# mic-preamp.net
KiCad netlist of a schematic drawn in EAGLE
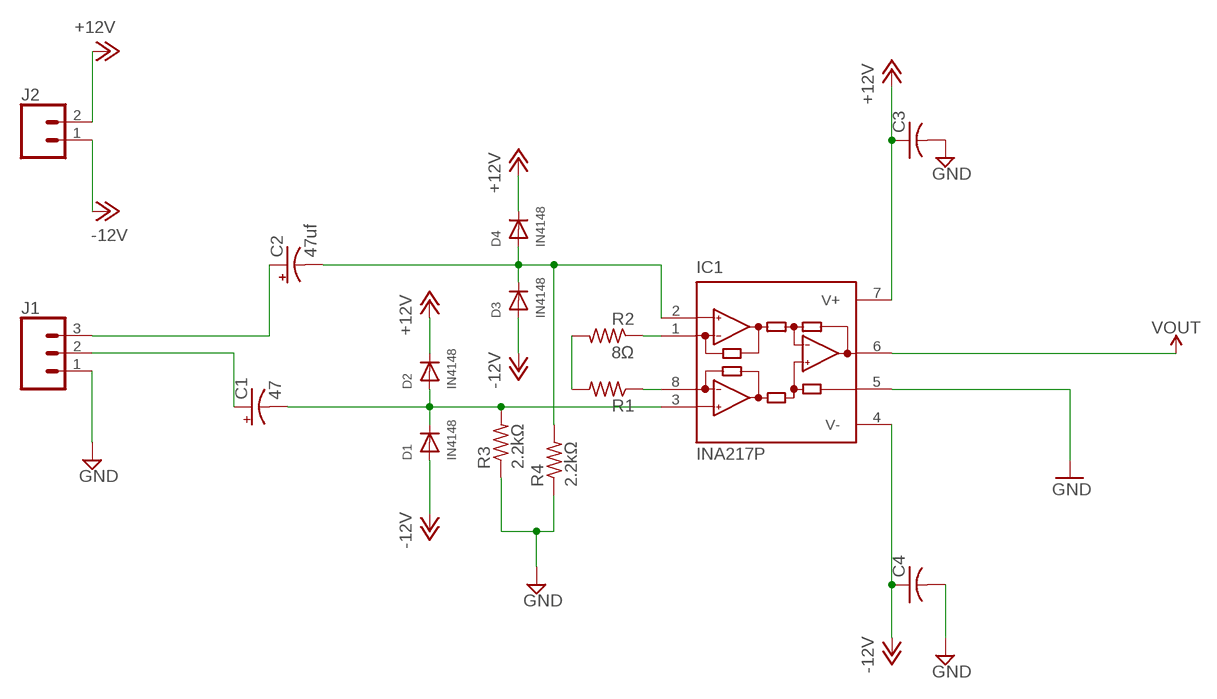
[diagram p0: schematic, sheet 1]

(export (version "E")
  (design (tool "Eeschema 10.0.6"))
  (components
    (comp (ref "C1")
      (value "47")
      (footprint "eagle-import:E7,5-16")
      (libsource (lib "eagle-import") (part "CPOL-USE7.5-16"))
    )
    (comp (ref "C2")
      (value "47uf")
      (footprint "eagle-import:E7,5-16")
      (libsource (lib "eagle-import") (part "CPOL-USE7.5-16"))
    )
    (comp (ref "C3")
      (value "C-US025-024X044")
      (footprint "eagle-import:C025-024X044")
      (libsource (lib "eagle-import") (part "C-US025-024X044"))
    )
    (comp (ref "C4")
      (value "C-US025-024X044")
      (footprint "eagle-import:C025-024X044")
      (libsource (lib "eagle-import") (part "C-US025-024X044"))
    )
    (comp (ref "D1")
      (value "IN4148")
      (footprint "eagle-import:DO-1N4148")
      (libsource (lib "eagle-import") (part "DIODEDO-1N4148"))
    )
    (comp (ref "D2")
      (value "IN4148")
      (footprint "eagle-import:DO-1N4148")
      (libsource (lib "eagle-import") (part "DIODEDO-1N4148"))
    )
    (comp (ref "D3")
      (value "IN4148")
      (footprint "eagle-import:DO-1N4148")
      (libsource (lib "eagle-import") (part "DIODEDO-1N4148"))
    )
    (comp (ref "D4")
      (value "IN4148")
      (footprint "eagle-import:DO-1N4148")
      (libsource (lib "eagle-import") (part "DIODEDO-1N4148"))
    )
    (comp (ref "IC1")
      (value "INA217P")
      (footprint "eagle-import:DIL08")
      (fields (field (name "MF") "TEXAS INSTRUMENTS") (field (name "MPN") "INA217AIP"))
      (libsource (lib "eagle-import") (part "INA217P"))
    )
    (comp (ref "J1")
      (value "CONN_03JST-PTH")
      (footprint "eagle-import:JST-3-PTH")
      (libsource (lib "eagle-import") (part "CONN_03JST-PTH"))
    )
    (comp (ref "J2")
      (value "CONN_02POLAR")
      (footprint "eagle-import:MOLEX-1X2")
      (libsource (lib "eagle-import") (part "CONN_02POLAR"))
    )
    (comp (ref "R1")
      (value "R-US_0204/7")
      (footprint "eagle-import:0204_7")
      (libsource (lib "eagle-import") (part "R-US_0204/7"))
    )
    (comp (ref "R2")
      (value "8Ω")
      (footprint "eagle-import:0204_7")
      (libsource (lib "eagle-import") (part "R-US_0204/7"))
    )
    (comp (ref "R3")
      (value "2.2kΩ")
      (footprint "eagle-import:0204_7")
      (libsource (lib "eagle-import") (part "R-US_0204/7"))
    )
    (comp (ref "R4")
      (value "2.2kΩ")
      (footprint "eagle-import:0204_7")
      (libsource (lib "eagle-import") (part "R-US_0204/7"))
    )
  )
  (nets
    (net (code "1") (name "+12V") (class "Default")
      (node (ref "C3") (pin "1") (pinfunction "1_1") (pintype "passive"))
      (node (ref "D2") (pin "C") (pinfunction "C_C") (pintype "passive"))
      (node (ref "D4") (pin "C") (pinfunction "C_C") (pintype "passive"))
      (node (ref "IC1") (pin "7") (pinfunction "V+_7") (pintype "power_in"))
      (node (ref "J2") (pin "2") (pinfunction "2_2") (pintype "passive"))
    )
    (net (code "2") (name "-12V") (class "Default")
      (node (ref "C4") (pin "1") (pinfunction "1_1") (pintype "passive"))
      (node (ref "D1") (pin "A") (pinfunction "A_A") (pintype "passive"))
      (node (ref "D3") (pin "A") (pinfunction "A_A") (pintype "passive"))
      (node (ref "IC1") (pin "4") (pinfunction "V-_4") (pintype "power_in"))
      (node (ref "J2") (pin "1") (pinfunction "1_1") (pintype "passive"))
    )
    (net (code "3") (name "GND") (class "Default")
      (node (ref "C3") (pin "2") (pinfunction "2_2") (pintype "passive"))
      (node (ref "C4") (pin "2") (pinfunction "2_2") (pintype "passive"))
      (node (ref "IC1") (pin "5") (pinfunction "REF_5") (pintype "passive"))
      (node (ref "J1") (pin "1") (pinfunction "1_1") (pintype "passive"))
      (node (ref "R3") (pin "1") (pinfunction "1_1") (pintype "passive"))
      (node (ref "R4") (pin "1") (pinfunction "1_1") (pintype "passive"))
    )
    (net (code "4") (name "Net-(C1-Pad+)") (class "Default")
      (node (ref "C1") (pin "+") (pinfunction "+_+") (pintype "passive"))
      (node (ref "J1") (pin "2") (pinfunction "2_2") (pintype "passive"))
    )
    (net (code "5") (name "Net-(C2-Pad+)") (class "Default")
      (node (ref "C2") (pin "+") (pinfunction "+_+") (pintype "passive"))
      (node (ref "J1") (pin "3") (pinfunction "3_3") (pintype "passive"))
    )
    (net (code "6") (name "Net-(IC1-+IN)") (class "Default")
      (node (ref "C1") (pin "-") (pinfunction "-_-") (pintype "passive"))
      (node (ref "D1") (pin "C") (pinfunction "C_C") (pintype "passive"))
      (node (ref "D2") (pin "A") (pinfunction "A_A") (pintype "passive"))
      (node (ref "IC1") (pin "3") (pinfunction "+IN_3") (pintype "input"))
      (node (ref "R3") (pin "2") (pinfunction "2_2") (pintype "passive"))
    )
    (net (code "7") (name "Net-(IC1--IN)") (class "Default")
      (node (ref "C2") (pin "-") (pinfunction "-_-") (pintype "passive"))
      (node (ref "D3") (pin "C") (pinfunction "C_C") (pintype "passive"))
      (node (ref "D4") (pin "A") (pinfunction "A_A") (pintype "passive"))
      (node (ref "IC1") (pin "2") (pinfunction "-IN_2") (pintype "input"))
      (node (ref "R4") (pin "2") (pinfunction "2_2") (pintype "passive"))
    )
    (net (code "8") (name "Net-(IC1-RG1)") (class "Default")
      (node (ref "IC1") (pin "1") (pinfunction "RG1_1") (pintype "passive"))
      (node (ref "R2") (pin "1") (pinfunction "1_1") (pintype "passive"))
    )
    (net (code "9") (name "Net-(IC1-RG2)") (class "Default")
      (node (ref "IC1") (pin "8") (pinfunction "RG2_8") (pintype "passive"))
      (node (ref "R1") (pin "1") (pinfunction "1_1") (pintype "passive"))
    )
    (net (code "10") (name "Net-(R1-Pad2)") (class "Default")
      (node (ref "R1") (pin "2") (pinfunction "2_2") (pintype "passive"))
      (node (ref "R2") (pin "2") (pinfunction "2_2") (pintype "passive"))
    )
    (net (code "11") (name "VOUT") (class "Default")
      (node (ref "IC1") (pin "6") (pinfunction "OUT_6") (pintype "output"))
    )
  )
)
